# SpringX.net
KiCad netlist of a schematic drawn in EAGLE
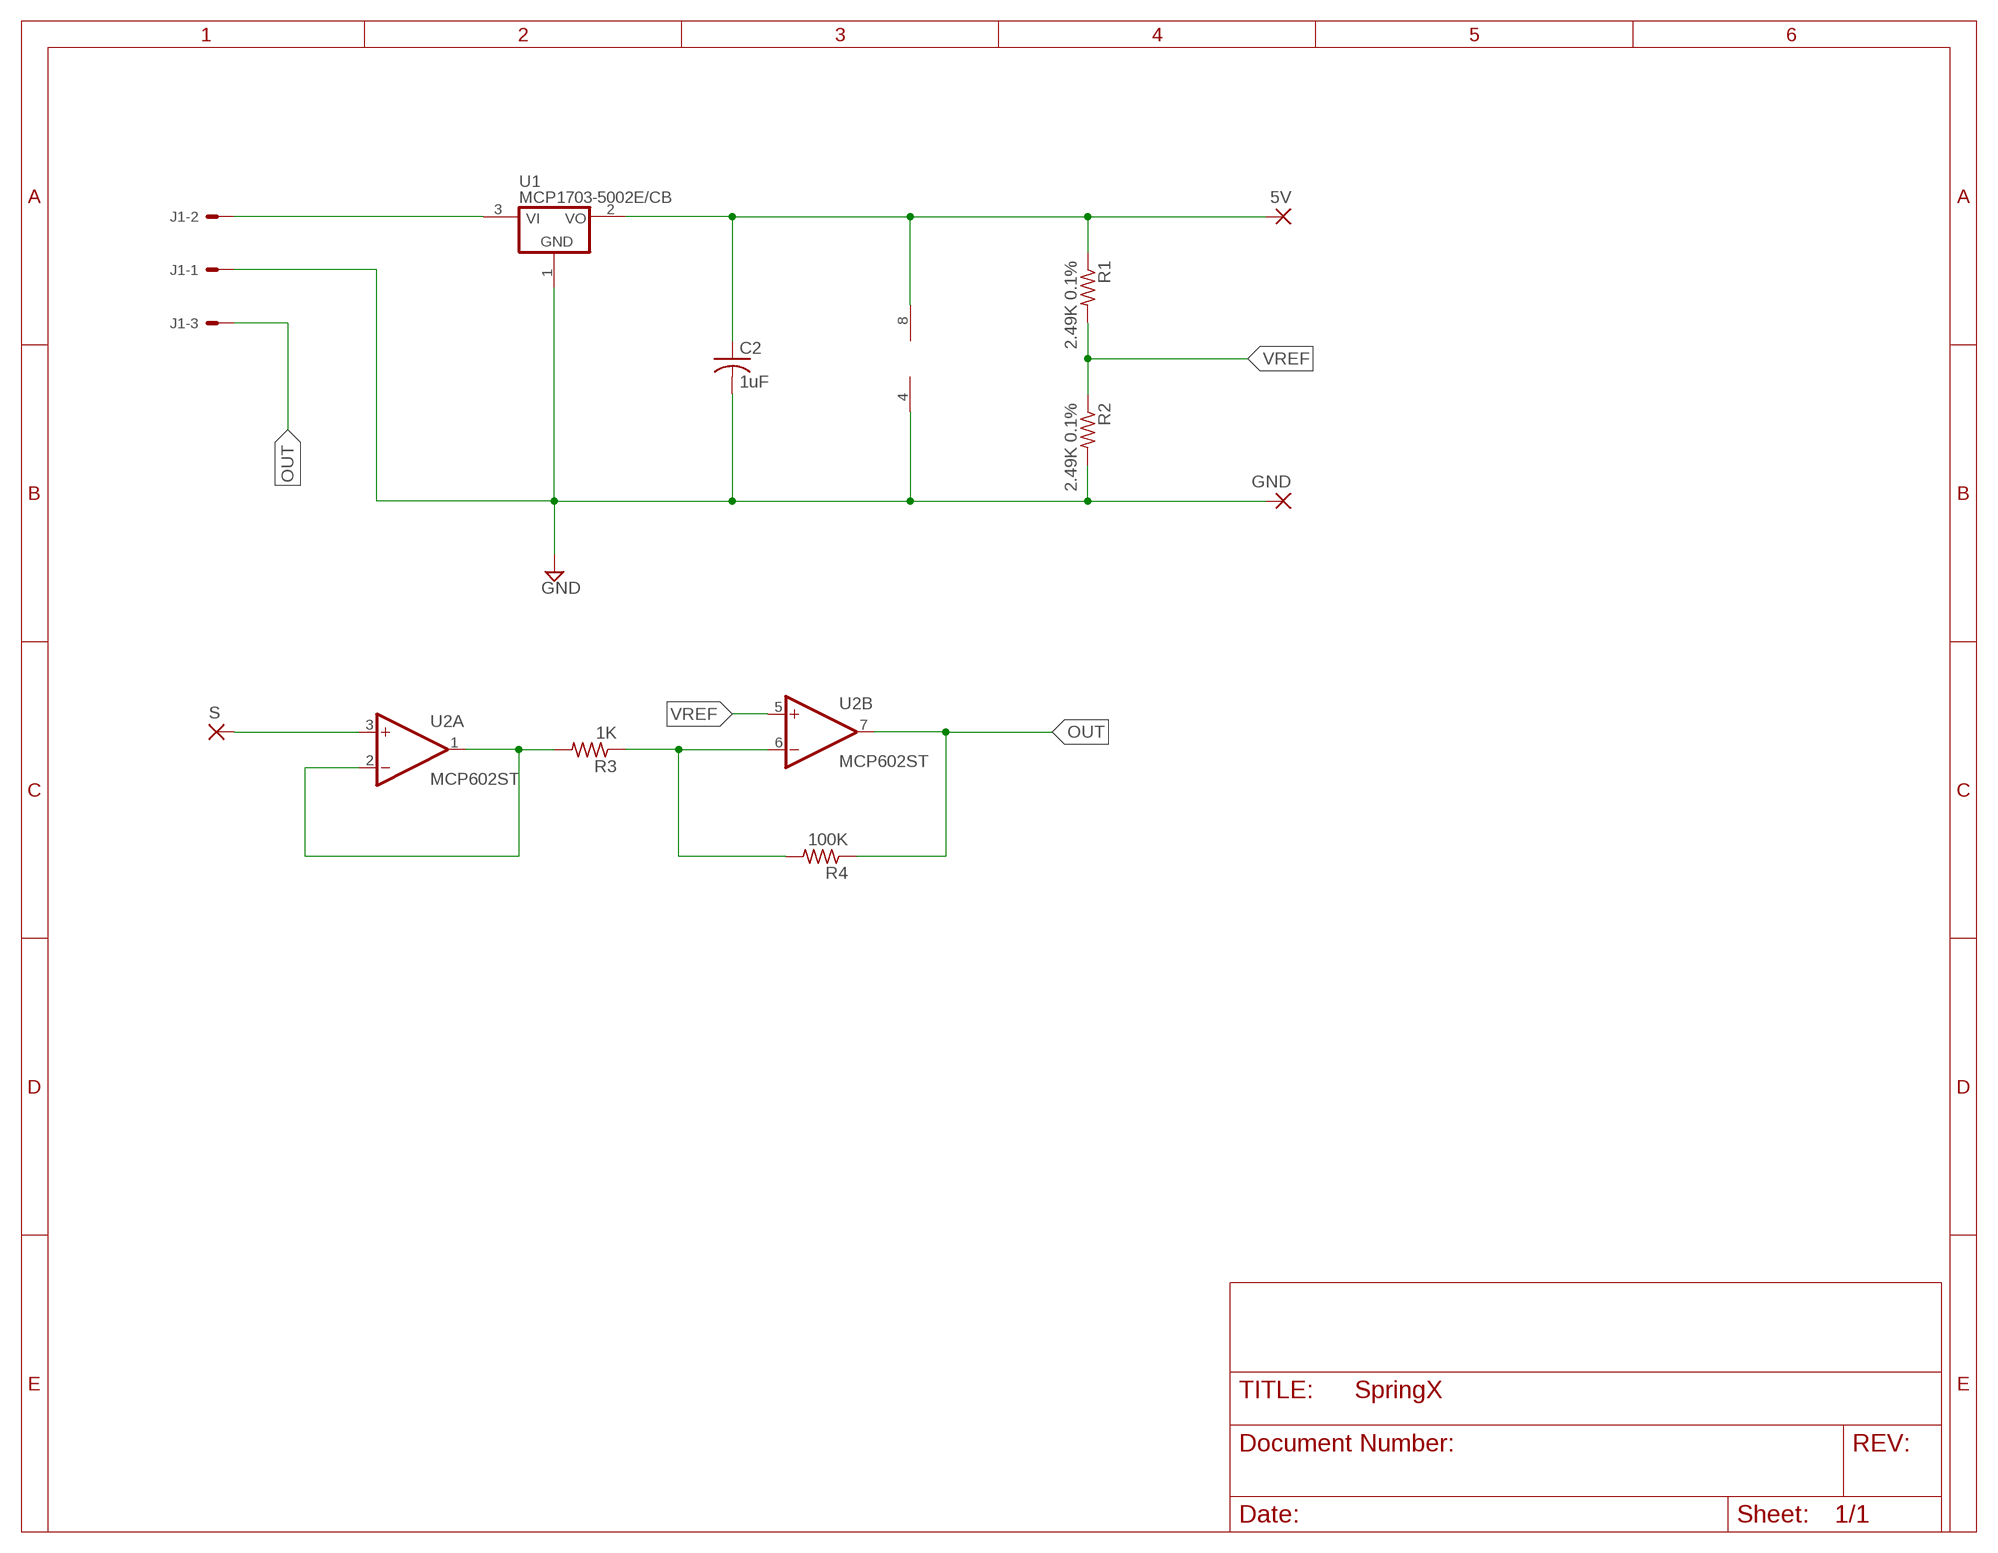
[diagram p0: schematic, sheet 1]

(export (version "E")
  (design (tool "Eeschema 10.0.6"))
  (components
    (comp (ref "5V")
      (value "2,15/1,0")
      (footprint "eagle-import:2,15_1,0")
      (libsource (lib "eagle-import") (part "2,15/1,0"))
    )
    (comp (ref "C2")
      (value "1uF")
      (footprint "eagle-import:C0603")
      (libsource (lib "eagle-import") (part "C-USC0603"))
    )
    (comp (ref "GND")
      (value "2,15/1,0")
      (footprint "eagle-import:2,15_1,0")
      (libsource (lib "eagle-import") (part "2,15/1,0"))
    )
    (comp (ref "J1")
      (value "22-05-7038-03")
      (footprint "eagle-import:7395-03")
      (libsource (lib "eagle-import") (part "22-?-0305-7038"))
    )
    (comp (ref "R1")
      (value "2.49K 0.1%")
      (footprint "eagle-import:R0603")
      (libsource (lib "eagle-import") (part "R-US_R0603"))
    )
    (comp (ref "R2")
      (value "2.49K 0.1%")
      (footprint "eagle-import:R0603")
      (libsource (lib "eagle-import") (part "R-US_R0603"))
    )
    (comp (ref "R3")
      (value "1K")
      (footprint "eagle-import:R0603")
      (libsource (lib "eagle-import") (part "R-US_R0603"))
    )
    (comp (ref "R4")
      (value "100K")
      (footprint "eagle-import:R0603")
      (libsource (lib "eagle-import") (part "R-US_R0603"))
    )
    (comp (ref "S")
      (value "2,15/1,0")
      (footprint "eagle-import:2,15_1,0")
      (libsource (lib "eagle-import") (part "2,15/1,0"))
    )
    (comp (ref "U1")
      (value "MCP1703-5002E/CB")
      (footprint "eagle-import:SOT23A_MICROCHIP_CB")
      (libsource (lib "eagle-import") (part "MCP170302E/CB-50"))
    )
    (comp (ref "U2")
      (value "MCP602ST")
      (footprint "eagle-import:TSSOP8")
      (libsource (lib "eagle-import") (part "MCP602ST"))
    )
  )
  (nets
    (net (code "1") (name "GND") (class "Default")
      (node (ref "C2") (pin "2") (pinfunction "2_2") (pintype "passive"))
      (node (ref "GND") (pin "1") (pinfunction "P_1") (pintype "passive"))
      (node (ref "J1") (pin "1") (pinfunction "S_1") (pintype "passive"))
      (node (ref "R2") (pin "2") (pinfunction "2_2") (pintype "passive"))
      (node (ref "U1") (pin "1") (pinfunction "GND_1") (pintype "power_in"))
      (node (ref "U2") (pin "4") (pinfunction "V-_4") (pintype "power_in"))
    )
    (net (code "2") (name "Net-(5V-P)") (class "Default")
      (node (ref "5V") (pin "1") (pinfunction "P_1") (pintype "passive"))
      (node (ref "C2") (pin "1") (pinfunction "1_1") (pintype "passive"))
      (node (ref "R1") (pin "1") (pinfunction "1_1") (pintype "passive"))
      (node (ref "U1") (pin "2") (pinfunction "VO_2") (pintype "passive"))
      (node (ref "U2") (pin "8") (pinfunction "V+_8") (pintype "power_in"))
    )
    (net (code "3") (name "Net-(J1B-S)") (class "Default")
      (node (ref "J1") (pin "2") (pinfunction "S_2") (pintype "passive"))
      (node (ref "U1") (pin "3") (pinfunction "VI_3") (pintype "power_in"))
    )
    (net (code "4") (name "Net-(S-P)") (class "Default")
      (node (ref "S") (pin "1") (pinfunction "P_1") (pintype "passive"))
      (node (ref "U2") (pin "3") (pinfunction "+IN_3") (pintype "input"))
    )
    (net (code "5") (name "Net-(U2A--IN)") (class "Default")
      (node (ref "R3") (pin "2") (pinfunction "2_2") (pintype "passive"))
      (node (ref "U2") (pin "1") (pinfunction "OUT_1") (pintype "output"))
      (node (ref "U2") (pin "2") (pinfunction "-IN_2") (pintype "input"))
    )
    (net (code "6") (name "Net-(U2B--IN)") (class "Default")
      (node (ref "R3") (pin "1") (pinfunction "1_1") (pintype "passive"))
      (node (ref "R4") (pin "2") (pinfunction "2_2") (pintype "passive"))
      (node (ref "U2") (pin "6") (pinfunction "-IN_6") (pintype "input"))
    )
    (net (code "7") (name "OUT") (class "Default")
      (node (ref "J1") (pin "3") (pinfunction "S_3") (pintype "passive"))
      (node (ref "R4") (pin "1") (pinfunction "1_1") (pintype "passive"))
      (node (ref "U2") (pin "7") (pinfunction "OUT_7") (pintype "output"))
    )
    (net (code "8") (name "VREF") (class "Default")
      (node (ref "R1") (pin "2") (pinfunction "2_2") (pintype "passive"))
      (node (ref "R2") (pin "1") (pinfunction "1_1") (pintype "passive"))
      (node (ref "U2") (pin "5") (pinfunction "+IN_5") (pintype "input"))
    )
  )
)
